# Sheet0-MCU.net
KiCad netlist of a schematic drawn in Altium Designer
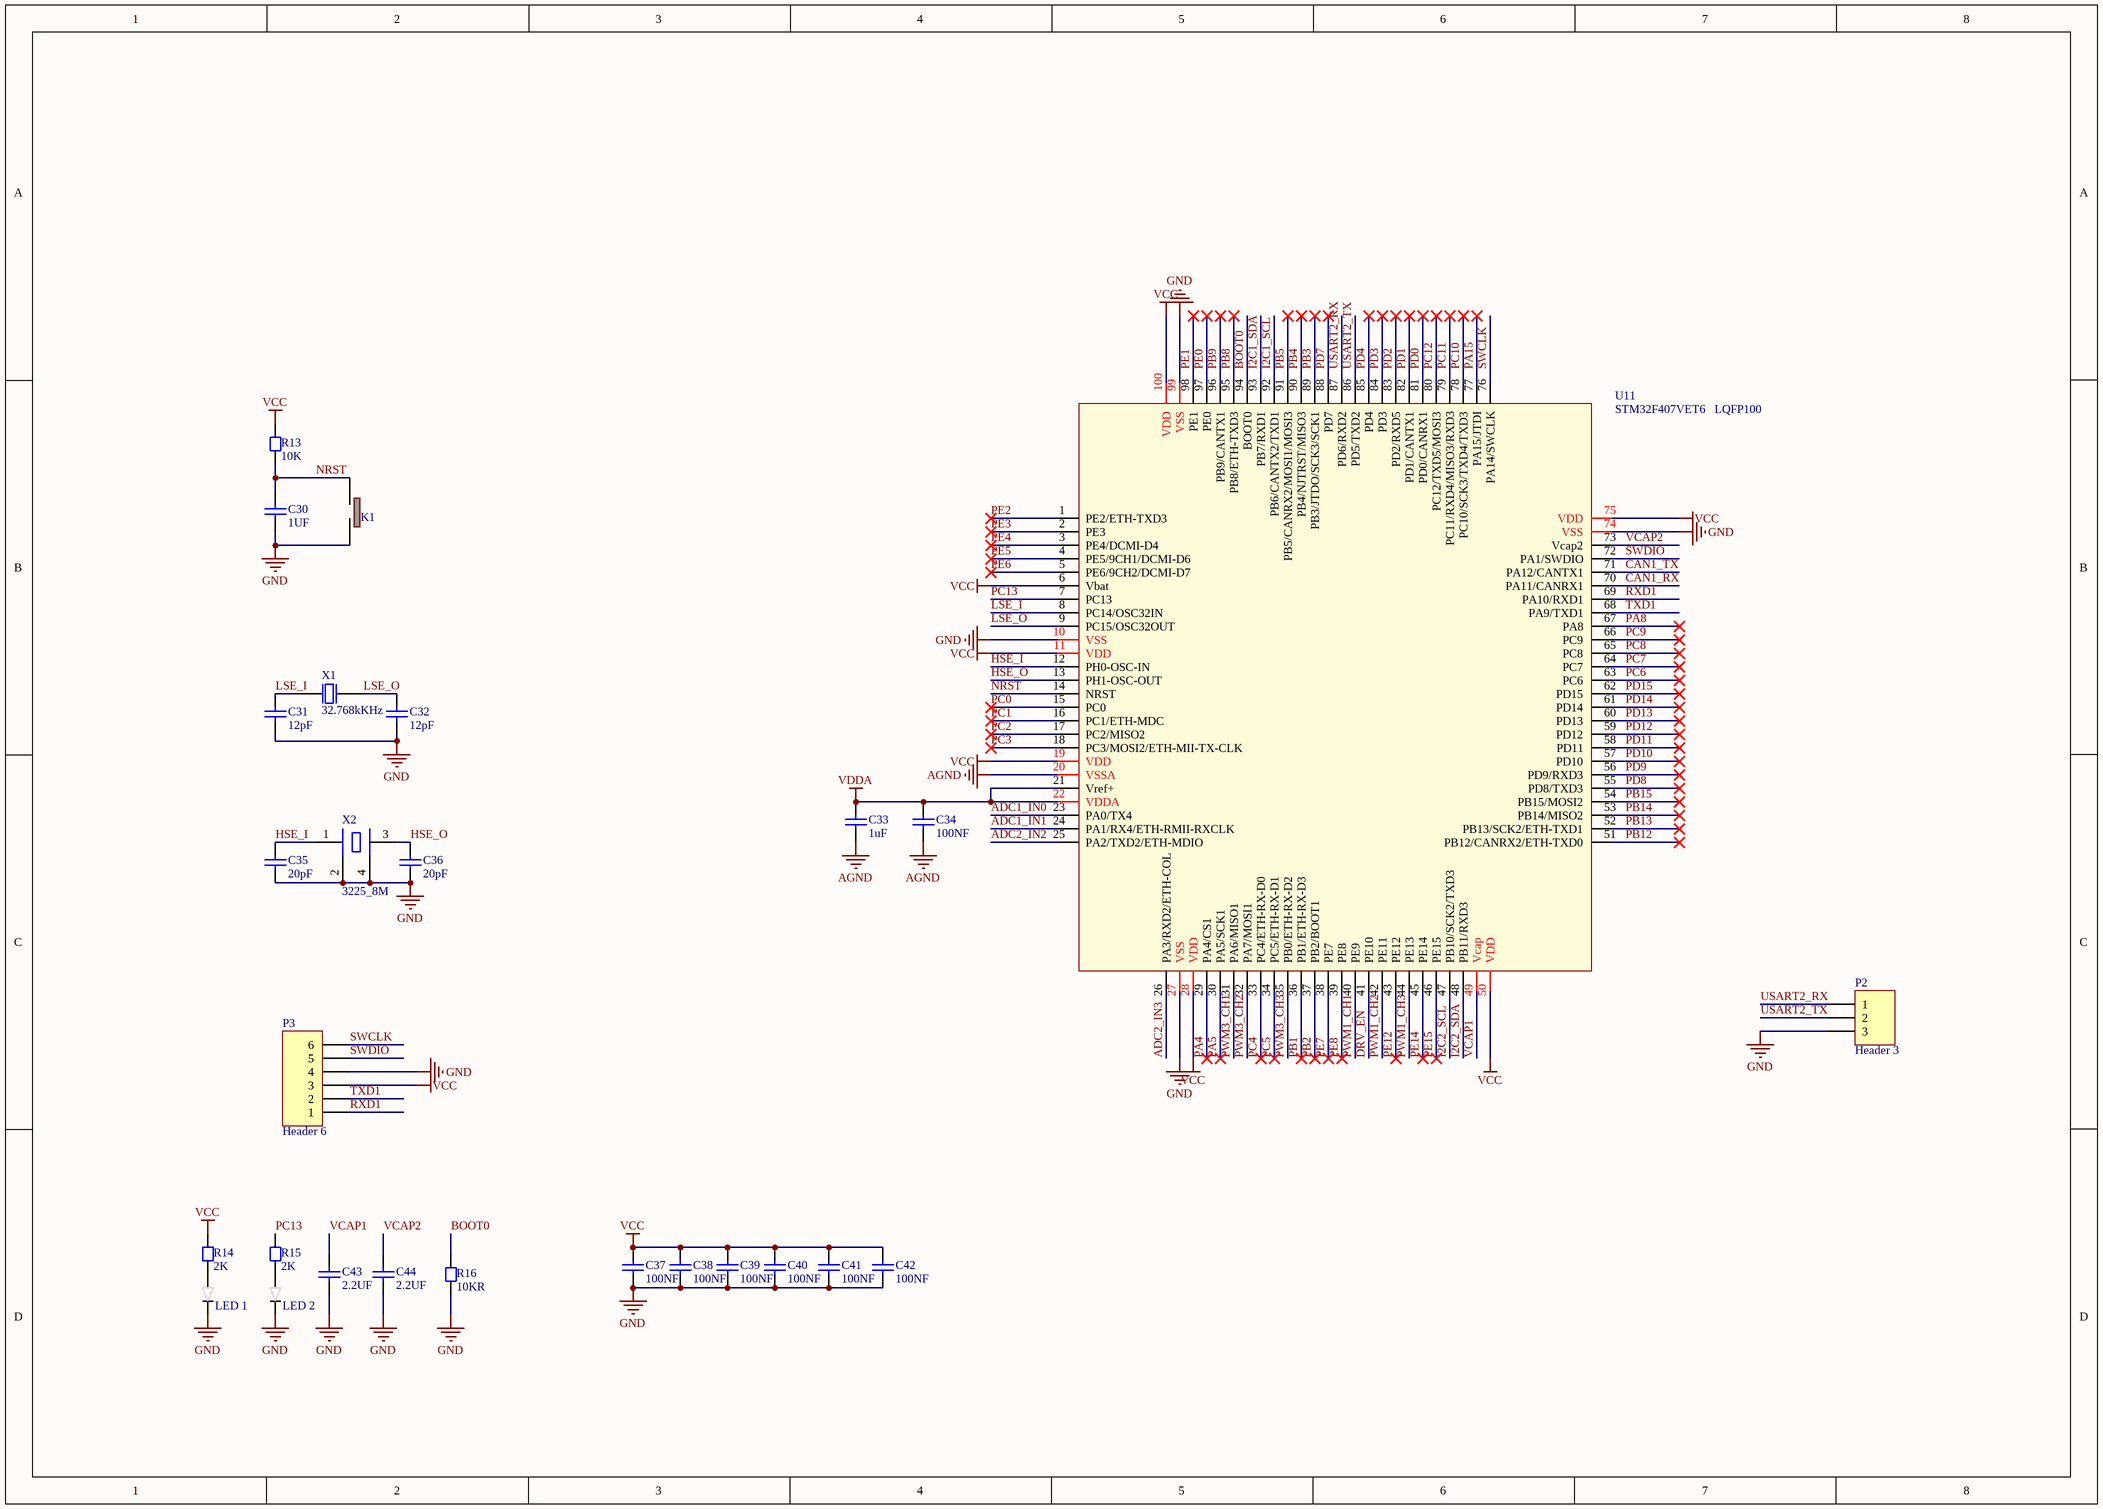
[diagram p0: Sheet0-MCU.SchDoc]

(export (version "E")
  (design (tool "Eeschema 10.0.6"))
  (components
    (comp (ref "C30")
      (value "1UF")
      (footprint "CC1608-0603")
      (description "0603封装的电容")
      (fields (field (name "PUBLISHER") "Altium Limited"))
      (libsource (lib "base") (part "Cap Chip 0603"))
    )
    (comp (ref "C31")
      (value "12pF")
      (footprint "CC1608-0603")
      (description "0603封装的电容")
      (fields (field (name "PUBLISHER") "Altium Limited"))
      (libsource (lib "base") (part "Cap Chip 0603"))
    )
    (comp (ref "C32")
      (value "12pF")
      (footprint "CC1608-0603")
      (description "0603封装的电容")
      (fields (field (name "PUBLISHER") "Altium Limited"))
      (libsource (lib "base") (part "Cap Chip 0603"))
    )
    (comp (ref "C33")
      (value "1uF")
      (footprint "CC1608-0603")
      (description "0603封装的电容")
      (fields (field (name "PUBLISHER") "Altium Limited"))
      (libsource (lib "base") (part "Cap Chip 0603"))
    )
    (comp (ref "C34")
      (value "100NF")
      (footprint "CC1608-0603")
      (description "0603封装的电容")
      (fields (field (name "PUBLISHER") "Altium Limited"))
      (libsource (lib "base") (part "Cap Chip 0603"))
    )
    (comp (ref "C35")
      (value "20pF")
      (footprint "CC1608-0603")
      (description "0603封装的电容")
      (fields (field (name "PUBLISHER") "Altium Limited"))
      (libsource (lib "base") (part "Cap Chip 0603"))
    )
    (comp (ref "C36")
      (value "20pF")
      (footprint "CC1608-0603")
      (description "0603封装的电容")
      (fields (field (name "PUBLISHER") "Altium Limited"))
      (libsource (lib "base") (part "Cap Chip 0603"))
    )
    (comp (ref "C37")
      (value "100NF")
      (footprint "CC1608-0603")
      (description "0603封装的电容")
      (fields (field (name "PUBLISHER") "Altium Limited"))
      (libsource (lib "base") (part "Cap Chip 0603"))
    )
    (comp (ref "C38")
      (value "100NF")
      (footprint "CC1608-0603")
      (description "0603封装的电容")
      (fields (field (name "PUBLISHER") "Altium Limited"))
      (libsource (lib "base") (part "Cap Chip 0603"))
    )
    (comp (ref "C39")
      (value "100NF")
      (footprint "CC1608-0603")
      (description "0603封装的电容")
      (fields (field (name "PUBLISHER") "Altium Limited"))
      (libsource (lib "base") (part "Cap Chip 0603"))
    )
    (comp (ref "C40")
      (value "100NF")
      (footprint "CC1608-0603")
      (description "0603封装的电容")
      (fields (field (name "PUBLISHER") "Altium Limited"))
      (libsource (lib "base") (part "Cap Chip 0603"))
    )
    (comp (ref "C41")
      (value "100NF")
      (footprint "CC1608-0603")
      (description "0603封装的电容")
      (fields (field (name "PUBLISHER") "Altium Limited"))
      (libsource (lib "base") (part "Cap Chip 0603"))
    )
    (comp (ref "C42")
      (value "100NF")
      (footprint "CC1608-0603")
      (description "0603封装的电容")
      (fields (field (name "PUBLISHER") "Altium Limited"))
      (libsource (lib "base") (part "Cap Chip 0603"))
    )
    (comp (ref "C43")
      (value "2.2UF")
      (footprint "CC1608-0603")
      (description "0603封装的电容")
      (fields (field (name "PUBLISHER") "Altium Limited"))
      (libsource (lib "base") (part "Cap Chip 0603"))
    )
    (comp (ref "C44")
      (value "2.2UF")
      (footprint "CC1608-0603")
      (description "0603封装的电容")
      (fields (field (name "PUBLISHER") "Altium Limited"))
      (libsource (lib "base") (part "Cap Chip 0603"))
    )
    (comp (ref "K1")
      (value "KEY 3*4")
      (footprint "KEY 3*4")
      (description "轻触开关按键")
      (libsource (lib "base") (part "KEY 3*4"))
    )
    (comp (ref "LED 1") (value "LED 0603") (footprint "LED 0603") (libsource (lib "base") (part "LED 0603")))
    (comp (ref "LED 2") (value "LED 0603") (footprint "LED 0603") (libsource (lib "base") (part "LED 0603")))
    (comp (ref "P2")
      (value "Header 3")
      (footprint "HX2.54-3")
      (description "Header, 3-Pin")
      (fields (field (name "PUBLISHER") "Altium Limited"))
      (libsource (lib "Connectors") (part "Header 3"))
    )
    (comp (ref "P3")
      (value "Header 6")
      (footprint "HDR1X6")
      (description "Header, 6-Pin")
      (fields (field (name "PUBLISHER") "Altium Limited"))
      (libsource (lib "Connectors") (part "Header 6"))
    )
    (comp (ref "R13")
      (value "10K")
      (footprint "CR1608-0603")
      (description "0603封装电阻")
      (fields (field (name "PUBLISHER") "Altium Limited"))
      (libsource (lib "base") (part "Resistor Chip 0603"))
    )
    (comp (ref "R14")
      (value "2K")
      (footprint "CR1608-0603")
      (description "0603封装电阻")
      (fields (field (name "PUBLISHER") "Altium Limited"))
      (libsource (lib "base") (part "Resistor Chip 0603"))
    )
    (comp (ref "R15")
      (value "2K")
      (footprint "CR1608-0603")
      (description "0603封装电阻")
      (fields (field (name "PUBLISHER") "Altium Limited"))
      (libsource (lib "base") (part "Resistor Chip 0603"))
    )
    (comp (ref "R16")
      (value "10KR")
      (footprint "CR1608-0603")
      (description "0603封装电阻")
      (fields (field (name "PUBLISHER") "Altium Limited"))
      (libsource (lib "base") (part "Resistor Chip 0603"))
    )
    (comp (ref "U11")
      (value "STM32F407VET6   LQFP100")
      (footprint "TQFP100")
      (description "168M单片机")
      (libsource (lib "singlechip") (part "STM32F407VET6"))
    )
    (comp (ref "X1")
      (value "32.768kKHz")
      (footprint "XTAL-3215")
      (description "3215封装的时钟晶振")
      (libsource (lib "base") (part "XTAL 3215 32.768kKHz"))
    )
    (comp (ref "X2")
      (value "3225_8M")
      (footprint "XTAL-3225")
      (description "3225封装的晶振")
      (libsource (lib "base") (part "XTAL 3225"))
    )
  )
  (nets
    (net (code "1") (name "/ADC1_IN0") (class "Default")
      (node (ref "U11") (pin "23") (pinfunction "PA0/TX4_23") (pintype "passive"))
    )
    (net (code "2") (name "/ADC1_IN1") (class "Default")
      (node (ref "U11") (pin "24") (pinfunction "PA1/RX4/ETH-RMII-RXCLK_24") (pintype "passive"))
    )
    (net (code "3") (name "/ADC2_IN2") (class "Default")
      (node (ref "U11") (pin "25") (pinfunction "PA2/TXD2/ETH-MDIO_25") (pintype "passive"))
    )
    (net (code "4") (name "/ADC2_IN3") (class "Default")
      (node (ref "U11") (pin "26") (pinfunction "PA3/RXD2/ETH-COL_26") (pintype "passive"))
    )
    (net (code "5") (name "/BOOT0") (class "Default")
      (node (ref "R16") (pin "2") (pinfunction "2_2") (pintype "passive"))
      (node (ref "U11") (pin "94") (pinfunction "BOOT0_94") (pintype "passive"))
    )
    (net (code "6") (name "/CAN1_RX") (class "Default")
      (node (ref "U11") (pin "70") (pinfunction "PA11/CANRX1_70") (pintype "passive"))
    )
    (net (code "7") (name "/CAN1_TX") (class "Default")
      (node (ref "U11") (pin "71") (pinfunction "PA12/CANTX1_71") (pintype "passive"))
    )
    (net (code "8") (name "/DRV_EN") (class "Default")
      (node (ref "U11") (pin "41") (pinfunction "PE10_41") (pintype "passive"))
    )
    (net (code "9") (name "/HSE_I") (class "Default")
      (node (ref "C35") (pin "2") (pinfunction "2_2") (pintype "passive"))
      (node (ref "U11") (pin "12") (pinfunction "PH0-OSC-IN_12") (pintype "passive"))
      (node (ref "X2") (pin "1") (pinfunction "OSC1_1") (pintype "passive"))
    )
    (net (code "10") (name "/HSE_O") (class "Default")
      (node (ref "C36") (pin "2") (pinfunction "2_2") (pintype "passive"))
      (node (ref "U11") (pin "13") (pinfunction "PH1-OSC-OUT_13") (pintype "passive"))
      (node (ref "X2") (pin "3") (pinfunction "OSC2_3") (pintype "passive"))
    )
    (net (code "11") (name "/I2C1_SCL") (class "Default")
      (node (ref "U11") (pin "92") (pinfunction "PB6/CANTX2/TXD1_92") (pintype "passive"))
    )
    (net (code "12") (name "/I2C1_SDA") (class "Default")
      (node (ref "U11") (pin "93") (pinfunction "PB7/RXD1_93") (pintype "passive"))
    )
    (net (code "13") (name "/I2C2_SCL") (class "Default")
      (node (ref "U11") (pin "47") (pinfunction "PB10/SCK2/TXD3_47") (pintype "passive"))
    )
    (net (code "14") (name "/I2C2_SDA") (class "Default")
      (node (ref "U11") (pin "48") (pinfunction "PB11/RXD3_48") (pintype "passive"))
    )
    (net (code "15") (name "/LSE_I") (class "Default")
      (node (ref "C31") (pin "2") (pinfunction "2_2") (pintype "passive"))
      (node (ref "U11") (pin "8") (pinfunction "PC14/OSC32IN_8") (pintype "passive"))
      (node (ref "X1") (pin "1") (pinfunction "OSC1_1") (pintype "passive"))
    )
    (net (code "16") (name "/LSE_O") (class "Default")
      (node (ref "C32") (pin "2") (pinfunction "2_2") (pintype "passive"))
      (node (ref "U11") (pin "9") (pinfunction "PC15/OSC32OUT_9") (pintype "passive"))
      (node (ref "X1") (pin "2") (pinfunction "OSC2_2") (pintype "passive"))
    )
    (net (code "17") (name "/NRST") (class "Default")
      (node (ref "C30") (pin "2") (pinfunction "2_2") (pintype "passive"))
      (node (ref "K1") (pin "1") (pinfunction "1_1") (pintype "passive"))
      (node (ref "R13") (pin "1") (pinfunction "1_1") (pintype "passive"))
      (node (ref "U11") (pin "14") (pinfunction "NRST_14") (pintype "passive"))
    )
    (net (code "18") (name "/PA4") (class "Default")
      (node (ref "U11") (pin "29") (pinfunction "PA4/CS1_29") (pintype "passive+no_connect"))
    )
    (net (code "19") (name "/PA5") (class "Default")
      (node (ref "U11") (pin "30") (pinfunction "PA5/SCK1_30") (pintype "passive+no_connect"))
    )
    (net (code "20") (name "/PA8") (class "Default")
      (node (ref "U11") (pin "67") (pinfunction "PA8_67") (pintype "passive+no_connect"))
    )
    (net (code "21") (name "/PA15") (class "Default")
      (node (ref "U11") (pin "77") (pinfunction "PA15/JTDI_77") (pintype "passive+no_connect"))
    )
    (net (code "22") (name "/PB1") (class "Default")
      (node (ref "U11") (pin "36") (pinfunction "PB1/ETH-RX-D3_36") (pintype "passive+no_connect"))
    )
    (net (code "23") (name "/PB2") (class "Default")
      (node (ref "U11") (pin "37") (pinfunction "PB2/BOOT1_37") (pintype "passive+no_connect"))
    )
    (net (code "24") (name "/PB3") (class "Default")
      (node (ref "U11") (pin "89") (pinfunction "PB3/JTDO/SCK3/SCK1_89") (pintype "passive+no_connect"))
    )
    (net (code "25") (name "/PB4") (class "Default")
      (node (ref "U11") (pin "90") (pinfunction "PB4/NJTRST/MISO3_90") (pintype "passive+no_connect"))
    )
    (net (code "26") (name "/PB5") (class "Default")
      (node (ref "U11") (pin "91") (pinfunction "PB5/CANRX2/MOSI1/MOSI3_91") (pintype "passive+no_connect"))
    )
    (net (code "27") (name "/PB8") (class "Default")
      (node (ref "U11") (pin "95") (pinfunction "PB8/ETH-TXD3_95") (pintype "passive+no_connect"))
    )
    (net (code "28") (name "/PB9") (class "Default")
      (node (ref "U11") (pin "96") (pinfunction "PB9/CANTX1_96") (pintype "passive+no_connect"))
    )
    (net (code "29") (name "/PB12") (class "Default")
      (node (ref "U11") (pin "51") (pinfunction "PB12/CANRX2/ETH-TXD0_51") (pintype "passive+no_connect"))
    )
    (net (code "30") (name "/PB13") (class "Default")
      (node (ref "U11") (pin "52") (pinfunction "PB13/SCK2/ETH-TXD1_52") (pintype "passive+no_connect"))
    )
    (net (code "31") (name "/PB14") (class "Default")
      (node (ref "U11") (pin "53") (pinfunction "PB14/MISO2_53") (pintype "passive+no_connect"))
    )
    (net (code "32") (name "/PB15") (class "Default")
      (node (ref "U11") (pin "54") (pinfunction "PB15/MOSI2_54") (pintype "passive+no_connect"))
    )
    (net (code "33") (name "/PC0") (class "Default")
      (node (ref "U11") (pin "15") (pinfunction "PC0_15") (pintype "passive+no_connect"))
    )
    (net (code "34") (name "/PC1") (class "Default")
      (node (ref "U11") (pin "16") (pinfunction "PC1/ETH-MDC_16") (pintype "passive+no_connect"))
    )
    (net (code "35") (name "/PC2") (class "Default")
      (node (ref "U11") (pin "17") (pinfunction "PC2/MISO2_17") (pintype "passive+no_connect"))
    )
    (net (code "36") (name "/PC3") (class "Default")
      (node (ref "U11") (pin "18") (pinfunction "PC3/MOSI2/ETH-MII-TX-CLK_18") (pintype "passive+no_connect"))
    )
    (net (code "37") (name "/PC4") (class "Default")
      (node (ref "U11") (pin "33") (pinfunction "PC4/ETH-RX-D0_33") (pintype "passive+no_connect"))
    )
    (net (code "38") (name "/PC5") (class "Default")
      (node (ref "U11") (pin "34") (pinfunction "PC5/ETH-RX-D1_34") (pintype "passive+no_connect"))
    )
    (net (code "39") (name "/PC6") (class "Default")
      (node (ref "U11") (pin "63") (pinfunction "PC6_63") (pintype "passive+no_connect"))
    )
    (net (code "40") (name "/PC7") (class "Default")
      (node (ref "U11") (pin "64") (pinfunction "PC7_64") (pintype "passive+no_connect"))
    )
    (net (code "41") (name "/PC8") (class "Default")
      (node (ref "U11") (pin "65") (pinfunction "PC8_65") (pintype "passive+no_connect"))
    )
    (net (code "42") (name "/PC9") (class "Default")
      (node (ref "U11") (pin "66") (pinfunction "PC9_66") (pintype "passive+no_connect"))
    )
    (net (code "43") (name "/PC10") (class "Default")
      (node (ref "U11") (pin "78") (pinfunction "PC10/SCK3/TXD4/TXD3_78") (pintype "passive+no_connect"))
    )
    (net (code "44") (name "/PC11") (class "Default")
      (node (ref "U11") (pin "79") (pinfunction "PC11/RXD4/MISO3/RXD3_79") (pintype "passive+no_connect"))
    )
    (net (code "45") (name "/PC12") (class "Default")
      (node (ref "U11") (pin "80") (pinfunction "PC12/TXD5/MOSI3_80") (pintype "passive+no_connect"))
    )
    (net (code "46") (name "/PC13") (class "Default")
      (node (ref "R15") (pin "2") (pinfunction "2_2") (pintype "passive"))
      (node (ref "U11") (pin "7") (pinfunction "PC13_7") (pintype "passive"))
    )
    (net (code "47") (name "/PD0") (class "Default")
      (node (ref "U11") (pin "81") (pinfunction "PD0/CANRX1_81") (pintype "passive+no_connect"))
    )
    (net (code "48") (name "/PD1") (class "Default")
      (node (ref "U11") (pin "82") (pinfunction "PD1/CANTX1_82") (pintype "passive+no_connect"))
    )
    (net (code "49") (name "/PD2") (class "Default")
      (node (ref "U11") (pin "83") (pinfunction "PD2/RXD5_83") (pintype "passive+no_connect"))
    )
    (net (code "50") (name "/PD3") (class "Default")
      (node (ref "U11") (pin "84") (pinfunction "PD3_84") (pintype "passive+no_connect"))
    )
    (net (code "51") (name "/PD4") (class "Default")
      (node (ref "U11") (pin "85") (pinfunction "PD4_85") (pintype "passive+no_connect"))
    )
    (net (code "52") (name "/PD7") (class "Default")
      (node (ref "U11") (pin "88") (pinfunction "PD7_88") (pintype "passive+no_connect"))
    )
    (net (code "53") (name "/PD8") (class "Default")
      (node (ref "U11") (pin "55") (pinfunction "PD8/TXD3_55") (pintype "passive+no_connect"))
    )
    (net (code "54") (name "/PD9") (class "Default")
      (node (ref "U11") (pin "56") (pinfunction "PD9/RXD3_56") (pintype "passive+no_connect"))
    )
    (net (code "55") (name "/PD10") (class "Default")
      (node (ref "U11") (pin "57") (pinfunction "PD10_57") (pintype "passive+no_connect"))
    )
    (net (code "56") (name "/PD11") (class "Default")
      (node (ref "U11") (pin "58") (pinfunction "PD11_58") (pintype "passive+no_connect"))
    )
    (net (code "57") (name "/PD12") (class "Default")
      (node (ref "U11") (pin "59") (pinfunction "PD12_59") (pintype "passive+no_connect"))
    )
    (net (code "58") (name "/PD13") (class "Default")
      (node (ref "U11") (pin "60") (pinfunction "PD13_60") (pintype "passive+no_connect"))
    )
    (net (code "59") (name "/PD14") (class "Default")
      (node (ref "U11") (pin "61") (pinfunction "PD14_61") (pintype "passive+no_connect"))
    )
    (net (code "60") (name "/PD15") (class "Default")
      (node (ref "U11") (pin "62") (pinfunction "PD15_62") (pintype "passive+no_connect"))
    )
    (net (code "61") (name "/PE0") (class "Default")
      (node (ref "U11") (pin "97") (pinfunction "PE0_97") (pintype "passive+no_connect"))
    )
    (net (code "62") (name "/PE1") (class "Default")
      (node (ref "U11") (pin "98") (pinfunction "PE1_98") (pintype "passive+no_connect"))
    )
    (net (code "63") (name "/PE2") (class "Default")
      (node (ref "U11") (pin "1") (pinfunction "PE2/ETH-TXD3_1") (pintype "passive+no_connect"))
    )
    (net (code "64") (name "/PE3") (class "Default")
      (node (ref "U11") (pin "2") (pinfunction "PE3_2") (pintype "passive+no_connect"))
    )
    (net (code "65") (name "/PE4") (class "Default")
      (node (ref "U11") (pin "3") (pinfunction "PE4/DCMI-D4_3") (pintype "passive+no_connect"))
    )
    (net (code "66") (name "/PE5") (class "Default")
      (node (ref "U11") (pin "4") (pinfunction "PE5/9CH1/DCMI-D6_4") (pintype "passive+no_connect"))
    )
    (net (code "67") (name "/PE6") (class "Default")
      (node (ref "U11") (pin "5") (pinfunction "PE6/9CH2/DCMI-D7_5") (pintype "passive+no_connect"))
    )
    (net (code "68") (name "/PE7") (class "Default")
      (node (ref "U11") (pin "38") (pinfunction "PE7_38") (pintype "passive+no_connect"))
    )
    (net (code "69") (name "/PE8") (class "Default")
      (node (ref "U11") (pin "39") (pinfunction "PE8_39") (pintype "passive+no_connect"))
    )
    (net (code "70") (name "/PE12") (class "Default")
      (node (ref "U11") (pin "43") (pinfunction "PE12_43") (pintype "passive+no_connect"))
    )
    (net (code "71") (name "/PE14") (class "Default")
      (node (ref "U11") (pin "45") (pinfunction "PE14_45") (pintype "passive+no_connect"))
    )
    (net (code "72") (name "/PE15") (class "Default")
      (node (ref "U11") (pin "46") (pinfunction "PE15_46") (pintype "passive+no_connect"))
    )
    (net (code "73") (name "/PWM1_CH1") (class "Default")
      (node (ref "U11") (pin "40") (pinfunction "PE9_40") (pintype "passive"))
    )
    (net (code "74") (name "/PWM1_CH2") (class "Default")
      (node (ref "U11") (pin "42") (pinfunction "PE11_42") (pintype "passive"))
    )
    (net (code "75") (name "/PWM1_CH3") (class "Default")
      (node (ref "U11") (pin "44") (pinfunction "PE13_44") (pintype "passive"))
    )
    (net (code "76") (name "/PWM3_CH1") (class "Default")
      (node (ref "U11") (pin "31") (pinfunction "PA6/MISO1_31") (pintype "passive"))
    )
    (net (code "77") (name "/PWM3_CH2") (class "Default")
      (node (ref "U11") (pin "32") (pinfunction "PA7/MOSI1_32") (pintype "passive"))
    )
    (net (code "78") (name "/PWM3_CH3") (class "Default")
      (node (ref "U11") (pin "35") (pinfunction "PB0/ETH-RX-D2_35") (pintype "passive"))
    )
    (net (code "79") (name "/RXD1") (class "Default")
      (node (ref "P3") (pin "1") (pinfunction "1_1") (pintype "passive"))
      (node (ref "U11") (pin "69") (pinfunction "PA10/RXD1_69") (pintype "passive"))
    )
    (net (code "80") (name "/SWCLK") (class "Default")
      (node (ref "P3") (pin "6") (pinfunction "6_6") (pintype "passive"))
      (node (ref "U11") (pin "76") (pinfunction "PA14/SWCLK_76") (pintype "passive"))
    )
    (net (code "81") (name "/SWDIO") (class "Default")
      (node (ref "P3") (pin "5") (pinfunction "5_5") (pintype "passive"))
      (node (ref "U11") (pin "72") (pinfunction "PA1/SWDIO_72") (pintype "passive"))
    )
    (net (code "82") (name "/TXD1") (class "Default")
      (node (ref "P3") (pin "2") (pinfunction "2_2") (pintype "passive"))
      (node (ref "U11") (pin "68") (pinfunction "PA9/TXD1_68") (pintype "passive"))
    )
    (net (code "83") (name "/USART2_RX") (class "Default")
      (node (ref "P2") (pin "1") (pinfunction "1_1") (pintype "passive"))
      (node (ref "U11") (pin "87") (pinfunction "PD6/RXD2_87") (pintype "passive"))
    )
    (net (code "84") (name "/USART2_TX") (class "Default")
      (node (ref "P2") (pin "2") (pinfunction "2_2") (pintype "passive"))
      (node (ref "U11") (pin "86") (pinfunction "PD5/TXD2_86") (pintype "passive"))
    )
    (net (code "85") (name "/VCAP1") (class "Default")
      (node (ref "C43") (pin "2") (pinfunction "2_2") (pintype "passive"))
      (node (ref "U11") (pin "49") (pinfunction "Vcap_49") (pintype "passive"))
    )
    (net (code "86") (name "/VCAP2") (class "Default")
      (node (ref "C44") (pin "2") (pinfunction "2_2") (pintype "passive"))
      (node (ref "U11") (pin "73") (pinfunction "Vcap2_73") (pintype "passive"))
    )
    (net (code "87") (name "AGND") (class "Default")
      (node (ref "C33") (pin "1") (pinfunction "1_1") (pintype "passive"))
      (node (ref "C34") (pin "1") (pinfunction "1_1") (pintype "passive"))
      (node (ref "U11") (pin "20") (pinfunction "VSSA_20") (pintype "passive"))
    )
    (net (code "88") (name "GND") (class "Default")
      (node (ref "C30") (pin "1") (pinfunction "1_1") (pintype "passive"))
      (node (ref "C31") (pin "1") (pinfunction "1_1") (pintype "passive"))
      (node (ref "C32") (pin "1") (pinfunction "1_1") (pintype "passive"))
      (node (ref "C35") (pin "1") (pinfunction "1_1") (pintype "passive"))
      (node (ref "C36") (pin "1") (pinfunction "1_1") (pintype "passive"))
      (node (ref "C37") (pin "1") (pinfunction "1_1") (pintype "passive"))
      (node (ref "C38") (pin "1") (pinfunction "1_1") (pintype "passive"))
      (node (ref "C39") (pin "1") (pinfunction "1_1") (pintype "passive"))
      (node (ref "C40") (pin "1") (pinfunction "1_1") (pintype "passive"))
      (node (ref "C41") (pin "1") (pinfunction "1_1") (pintype "passive"))
      (node (ref "C42") (pin "1") (pinfunction "1_1") (pintype "passive"))
      (node (ref "C43") (pin "1") (pinfunction "1_1") (pintype "passive"))
      (node (ref "C44") (pin "1") (pinfunction "1_1") (pintype "passive"))
      (node (ref "K1") (pin "2") (pinfunction "2_2") (pintype "passive"))
      (node (ref "LED 1") (pin "2") (pinfunction "2_2") (pintype "passive"))
      (node (ref "LED 2") (pin "2") (pinfunction "2_2") (pintype "passive"))
      (node (ref "P2") (pin "3") (pinfunction "3_3") (pintype "passive"))
      (node (ref "P3") (pin "4") (pinfunction "4_4") (pintype "passive"))
      (node (ref "R16") (pin "1") (pinfunction "1_1") (pintype "passive"))
      (node (ref "U11") (pin "10") (pinfunction "VSS_10") (pintype "passive"))
      (node (ref "U11") (pin "27") (pinfunction "VSS_27") (pintype "passive"))
      (node (ref "U11") (pin "74") (pinfunction "VSS_74") (pintype "passive"))
      (node (ref "U11") (pin "99") (pinfunction "VSS_99") (pintype "passive"))
      (node (ref "X2") (pin "2") (pinfunction "GND_2") (pintype "passive"))
      (node (ref "X2") (pin "4") (pinfunction "GND_4") (pintype "passive"))
    )
    (net (code "89") (name "Net-(LED 1-Pad1)") (class "Default")
      (node (ref "LED 1") (pin "1") (pinfunction "1_1") (pintype "passive"))
      (node (ref "R14") (pin "1") (pinfunction "1_1") (pintype "passive"))
    )
    (net (code "90") (name "Net-(LED 2-Pad1)") (class "Default")
      (node (ref "LED 2") (pin "1") (pinfunction "1_1") (pintype "passive"))
      (node (ref "R15") (pin "1") (pinfunction "1_1") (pintype "passive"))
    )
    (net (code "91") (name "VCC") (class "Default")
      (node (ref "C37") (pin "2") (pinfunction "2_2") (pintype "passive"))
      (node (ref "C38") (pin "2") (pinfunction "2_2") (pintype "passive"))
      (node (ref "C39") (pin "2") (pinfunction "2_2") (pintype "passive"))
      (node (ref "C40") (pin "2") (pinfunction "2_2") (pintype "passive"))
      (node (ref "C41") (pin "2") (pinfunction "2_2") (pintype "passive"))
      (node (ref "C42") (pin "2") (pinfunction "2_2") (pintype "passive"))
      (node (ref "P3") (pin "3") (pinfunction "3_3") (pintype "passive"))
      (node (ref "R13") (pin "2") (pinfunction "2_2") (pintype "passive"))
      (node (ref "R14") (pin "2") (pinfunction "2_2") (pintype "passive"))
      (node (ref "U11") (pin "100") (pinfunction "VDD_100") (pintype "passive"))
      (node (ref "U11") (pin "11") (pinfunction "VDD_11") (pintype "passive"))
      (node (ref "U11") (pin "19") (pinfunction "VDD_19") (pintype "passive"))
      (node (ref "U11") (pin "28") (pinfunction "VDD_28") (pintype "passive"))
      (node (ref "U11") (pin "50") (pinfunction "VDD_50") (pintype "passive"))
      (node (ref "U11") (pin "6") (pinfunction "Vbat_6") (pintype "passive"))
      (node (ref "U11") (pin "75") (pinfunction "VDD_75") (pintype "passive"))
    )
    (net (code "92") (name "VDDA") (class "Default")
      (node (ref "C33") (pin "2") (pinfunction "2_2") (pintype "passive"))
      (node (ref "C34") (pin "2") (pinfunction "2_2") (pintype "passive"))
      (node (ref "U11") (pin "21") (pinfunction "Vref+_21") (pintype "passive"))
      (node (ref "U11") (pin "22") (pinfunction "VDDA_22") (pintype "passive"))
    )
  )
)
